# envlogger.net
KiCad netlist of a schematic drawn in EAGLE
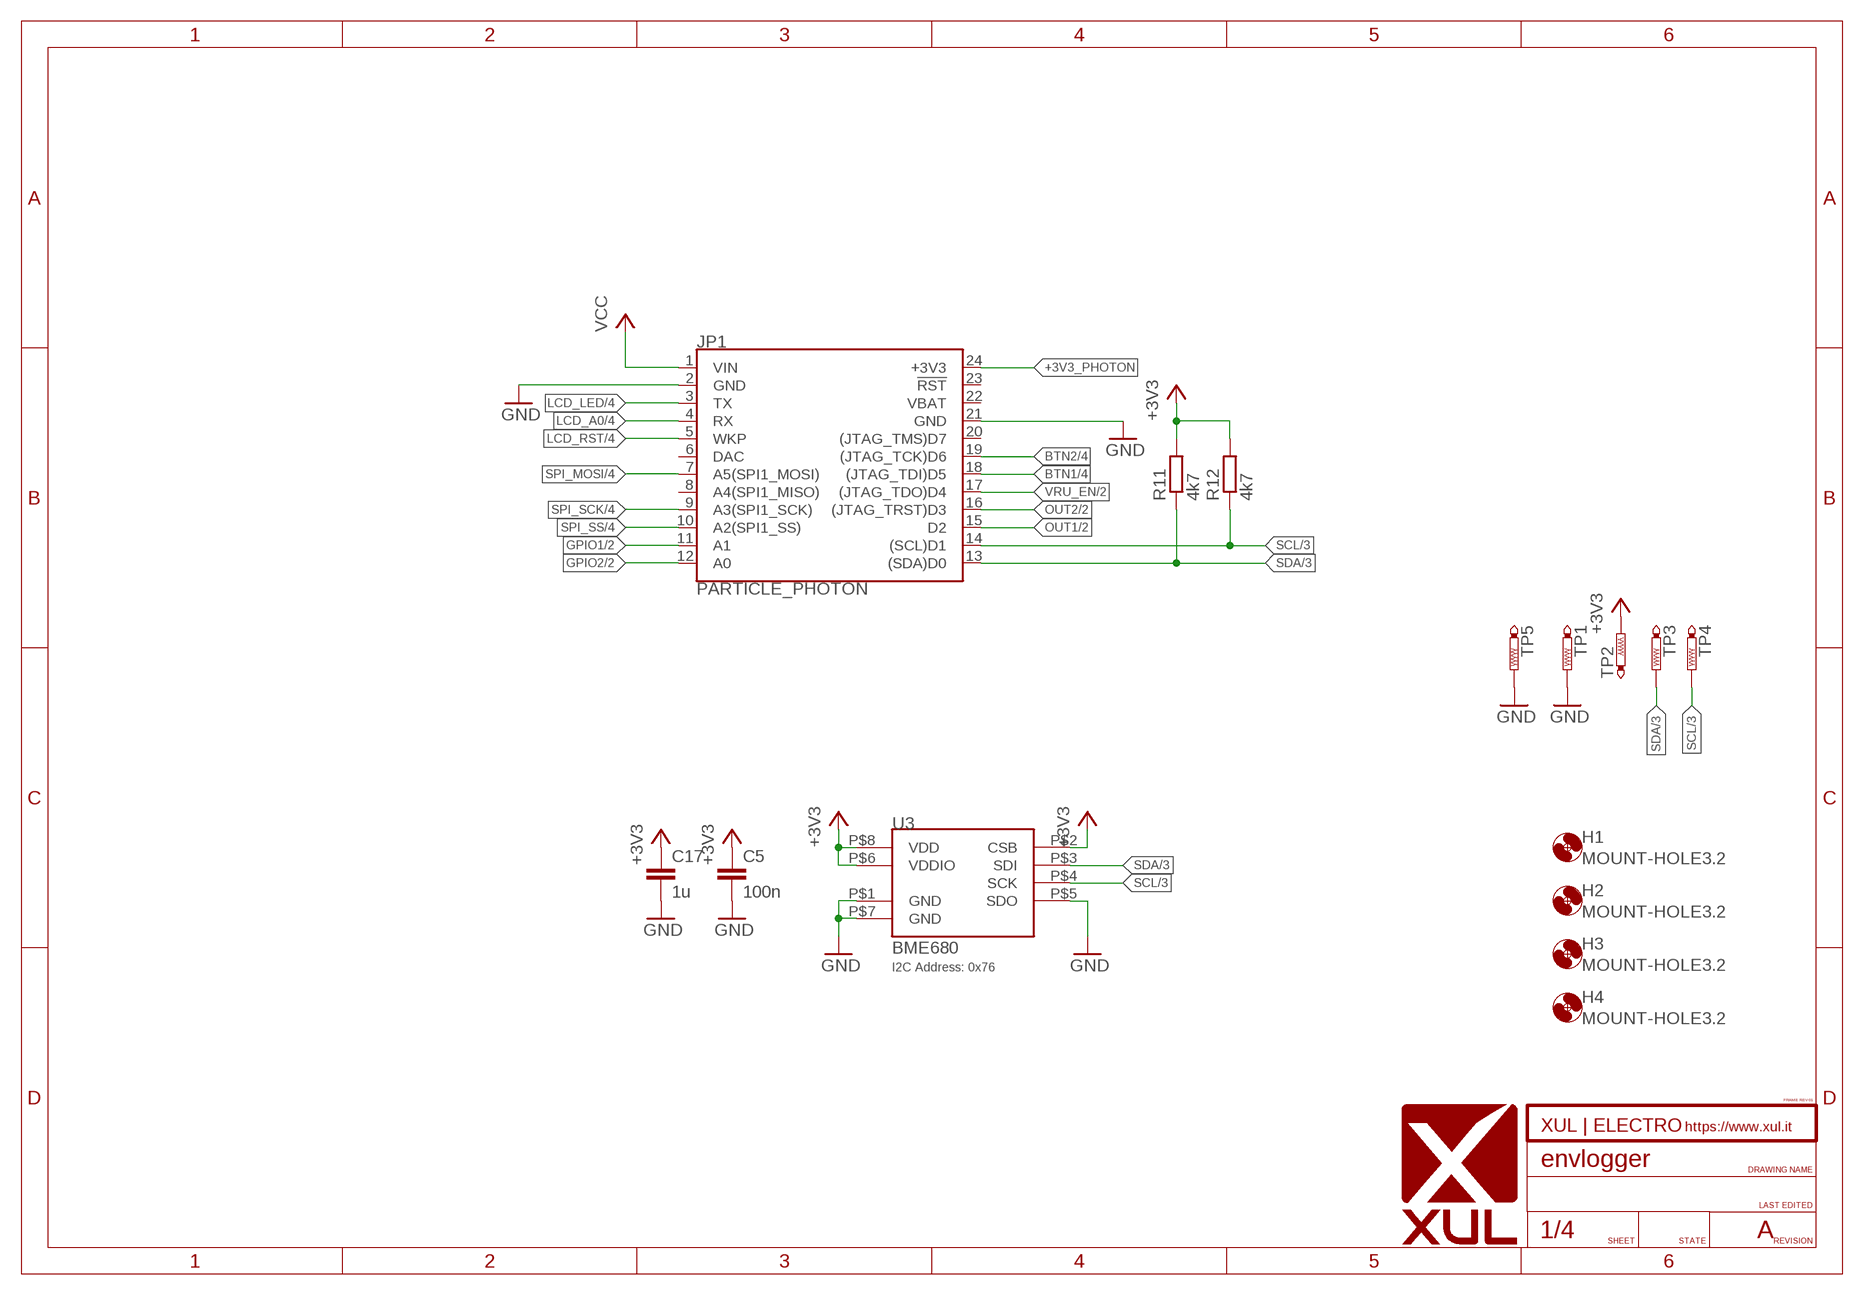
[diagram p0: schematic, sheet 1]
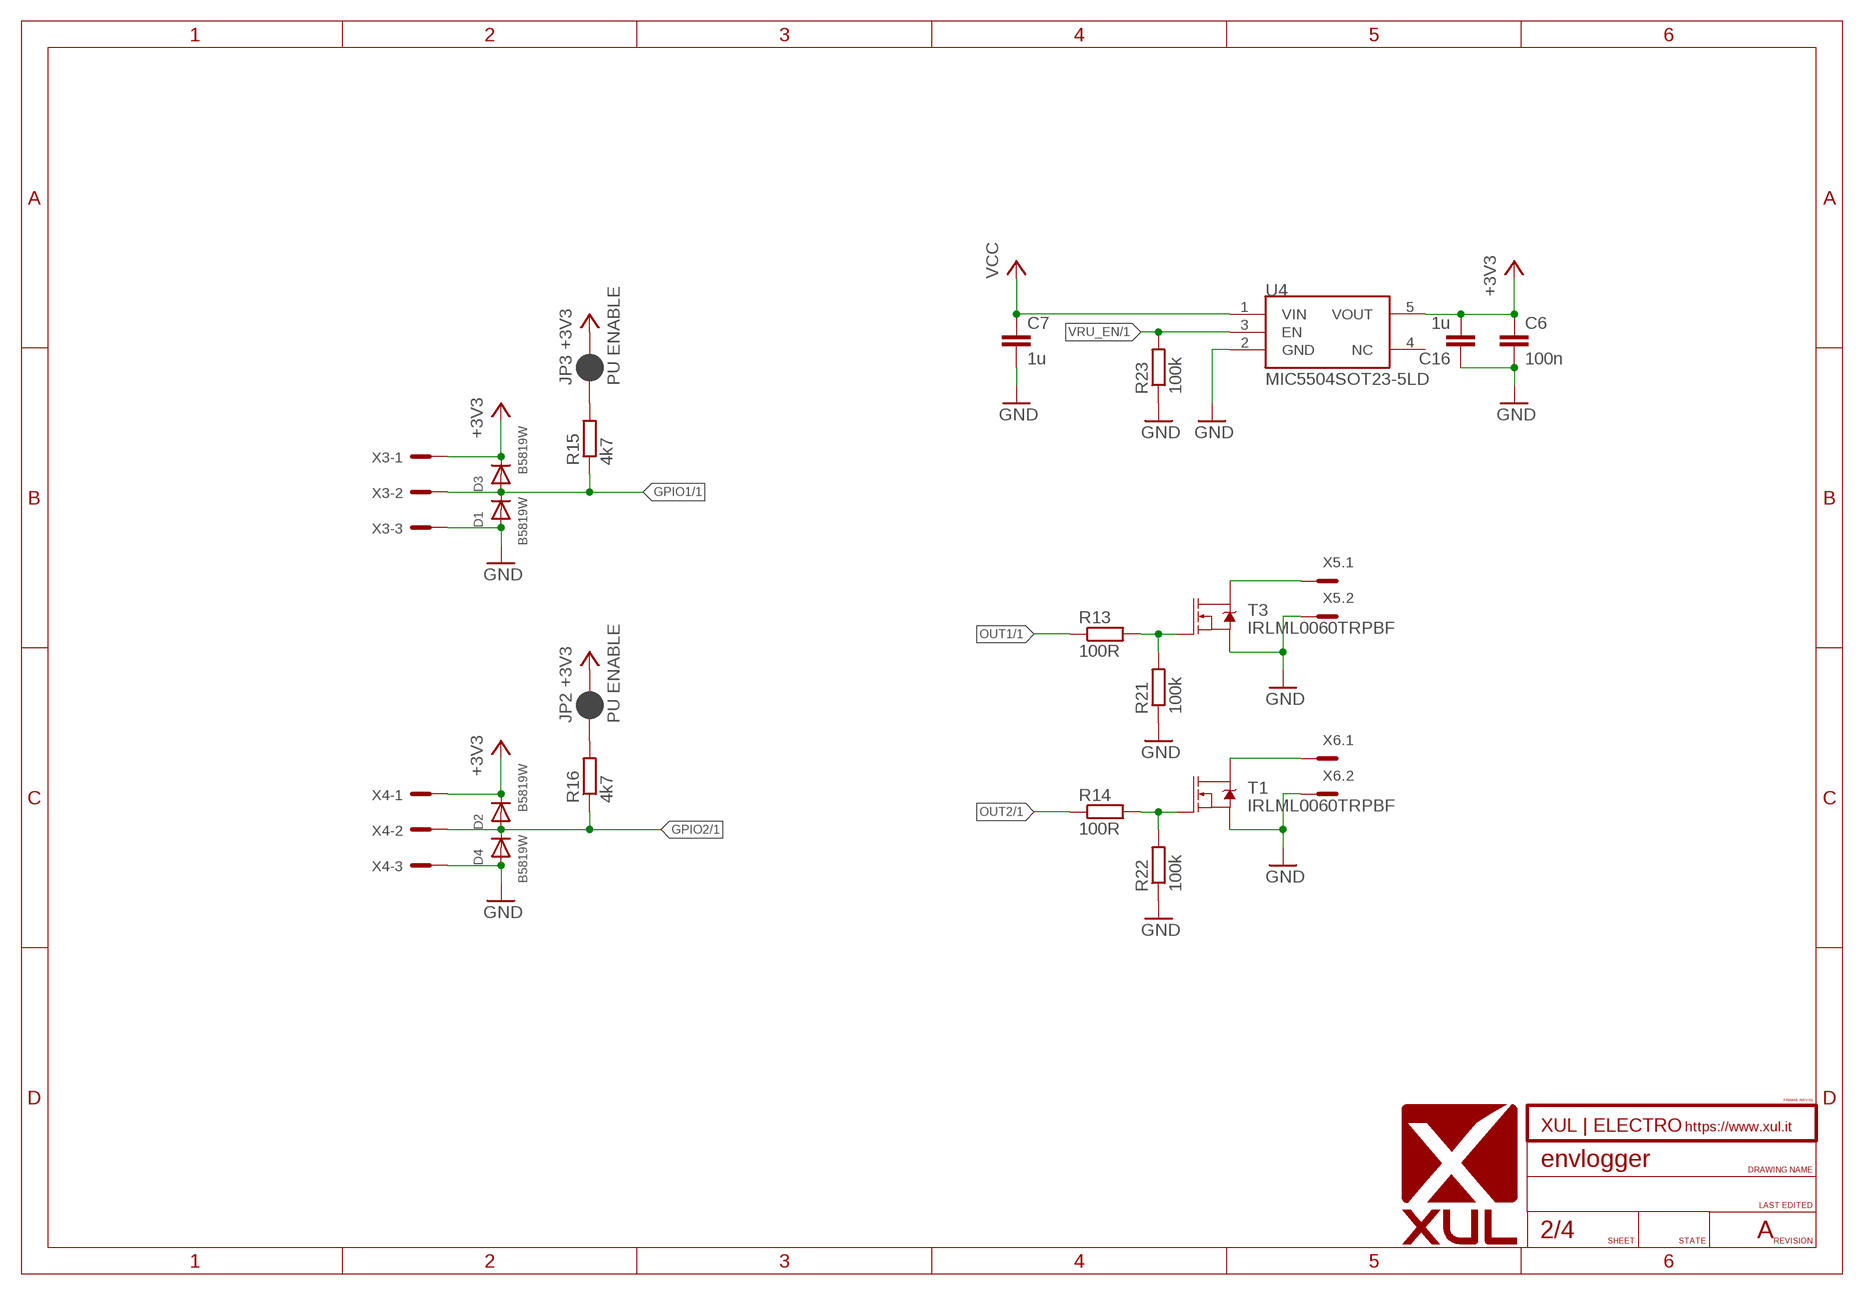
[diagram p1: schematic, sheet 2]
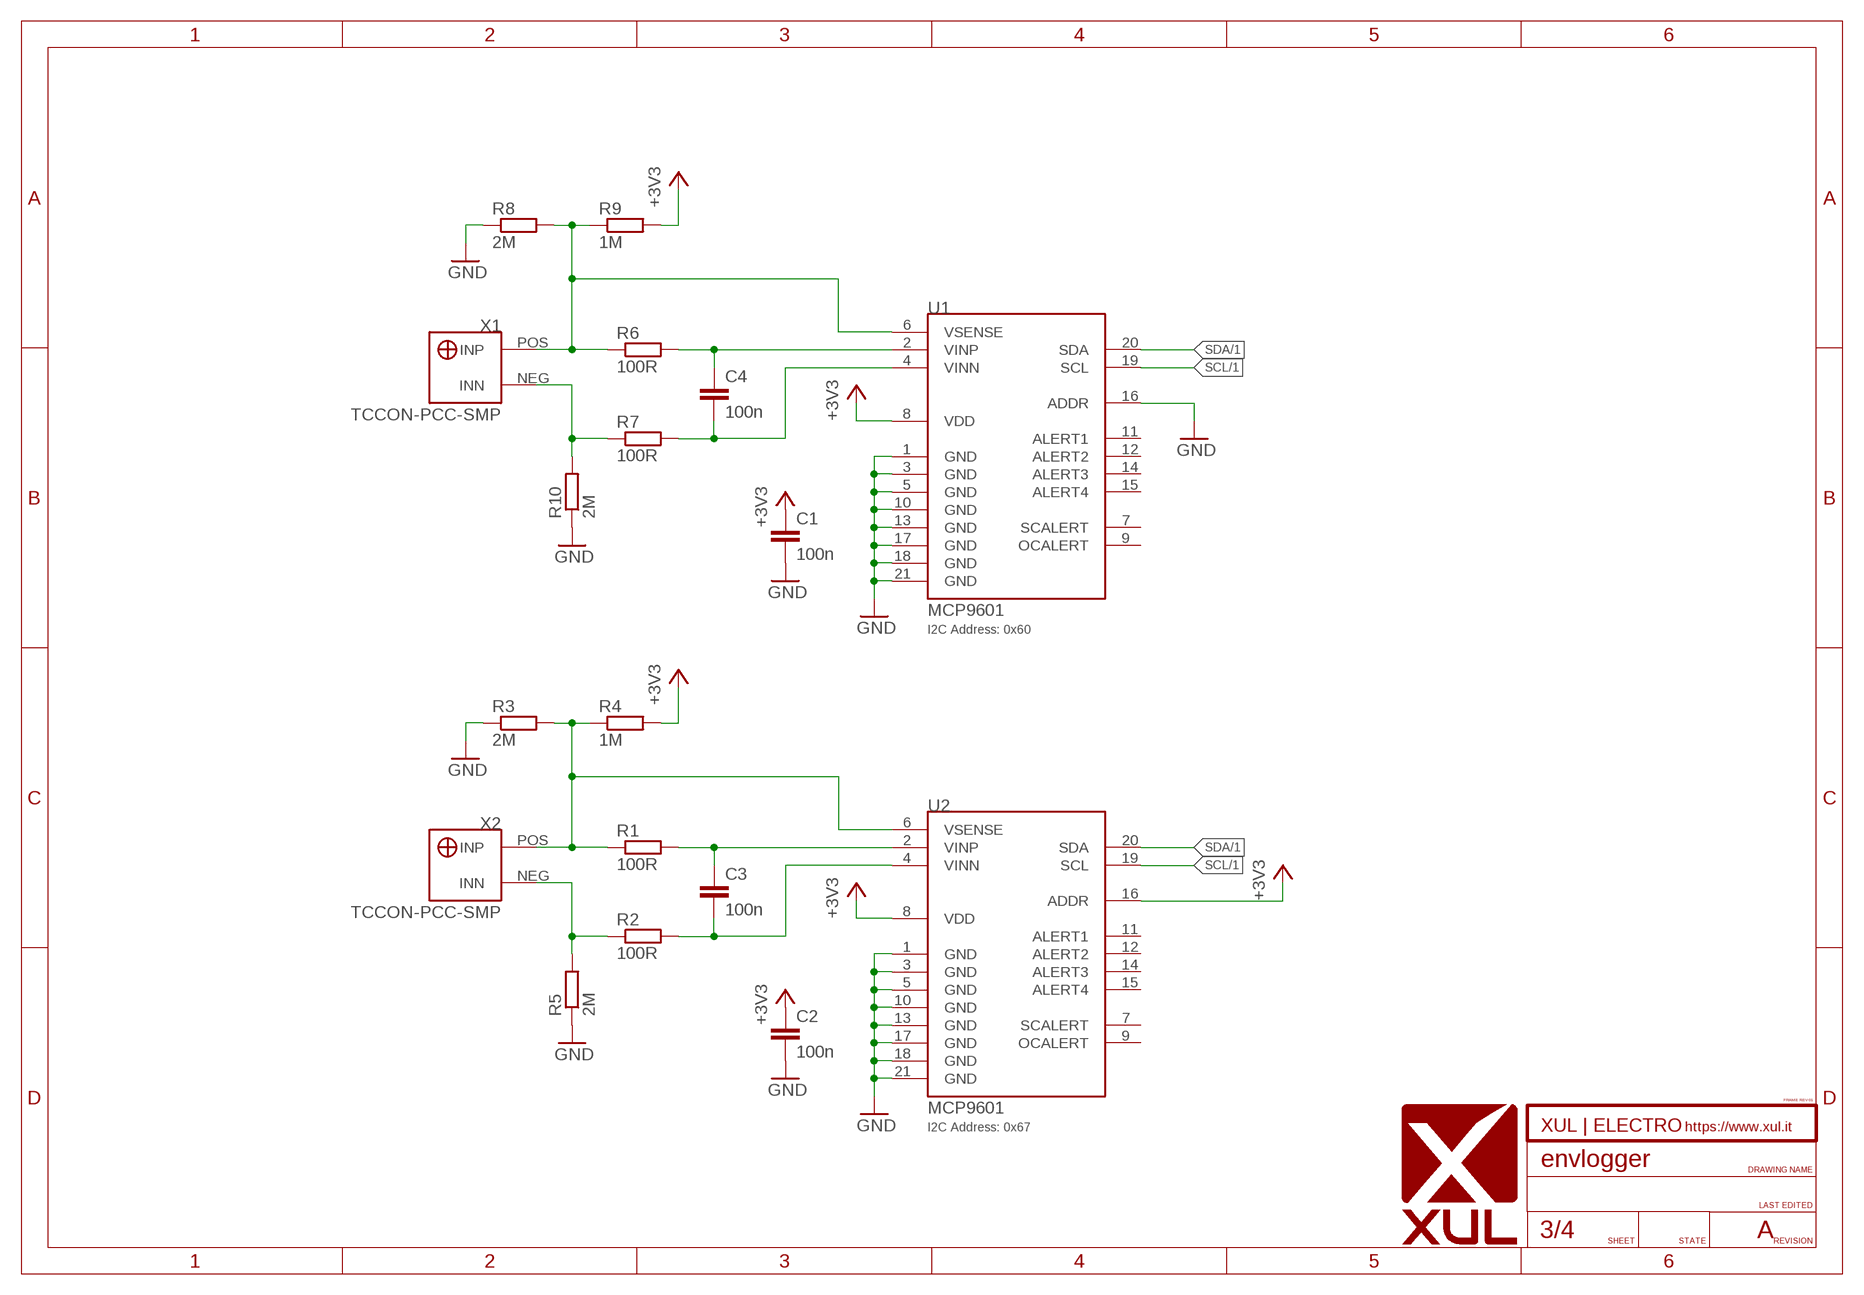
[diagram p2: schematic, sheet 3]
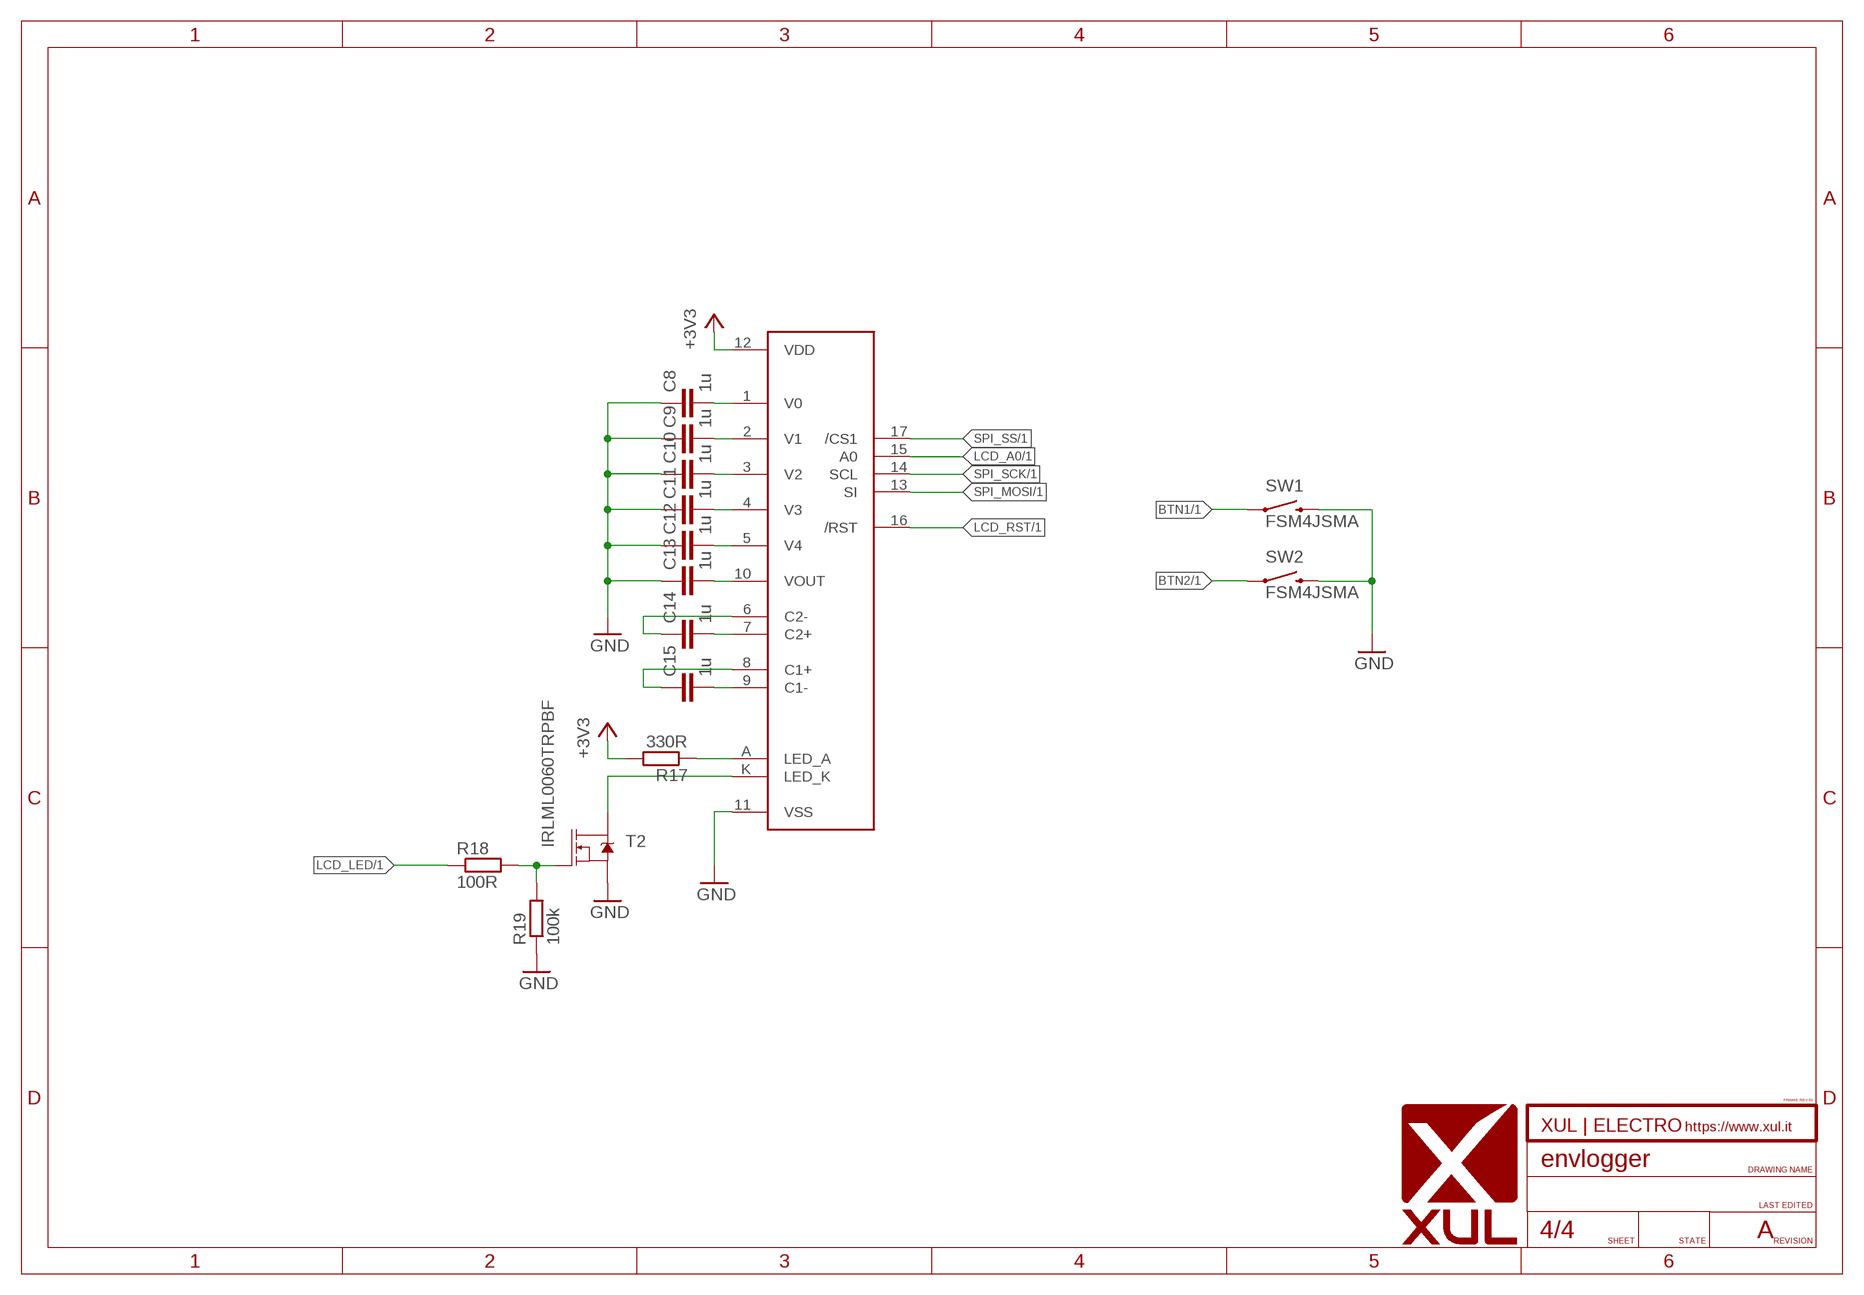
[diagram p3: schematic, sheet 4]

(export (version "E")
  (design (tool "Eeschema 10.0.6"))
  (components
    (comp (ref "C5")
      (value "100n")
      (footprint "eagle-import:C0603")
      (libsource (lib "eagle-import") (part "C-EUC0603"))
    )
    (comp (ref "C17")
      (value "1u")
      (footprint "eagle-import:C0603")
      (libsource (lib "eagle-import") (part "C-EUC0603"))
    )
    (comp (ref "H1")
      (value "MOUNT-HOLE3.2")
      (footprint "eagle-import:3,2")
      (libsource (lib "eagle-import") (part "MOUNT-HOLE3.2"))
    )
    (comp (ref "H2")
      (value "MOUNT-HOLE3.2")
      (footprint "eagle-import:3,2")
      (libsource (lib "eagle-import") (part "MOUNT-HOLE3.2"))
    )
    (comp (ref "H3")
      (value "MOUNT-HOLE3.2")
      (footprint "eagle-import:3,2")
      (libsource (lib "eagle-import") (part "MOUNT-HOLE3.2"))
    )
    (comp (ref "H4")
      (value "MOUNT-HOLE3.2")
      (footprint "eagle-import:3,2")
      (libsource (lib "eagle-import") (part "MOUNT-HOLE3.2"))
    )
    (comp (ref "JP1")
      (value "PARTICLE_PHOTON")
      (footprint "eagle-import:PARTICLE_PHOTON")
      (libsource (lib "eagle-import") (part "PARTICLE_PHOTON"))
    )
    (comp (ref "R11")
      (value "4k7")
      (footprint "eagle-import:R0603")
      (libsource (lib "eagle-import") (part "R-EU_R0603"))
    )
    (comp (ref "R12")
      (value "4k7")
      (footprint "eagle-import:R0603")
      (libsource (lib "eagle-import") (part "R-EU_R0603"))
    )
    (comp (ref "TP1")
      (value "PTR1B1,27")
      (footprint "eagle-import:B1,27")
      (libsource (lib "eagle-import") (part "PTR1B1,27"))
    )
    (comp (ref "TP2")
      (value "PTR1B1,27")
      (footprint "eagle-import:B1,27")
      (libsource (lib "eagle-import") (part "PTR1B1,27"))
    )
    (comp (ref "TP3")
      (value "PTR1B1,27")
      (footprint "eagle-import:B1,27")
      (libsource (lib "eagle-import") (part "PTR1B1,27"))
    )
    (comp (ref "TP4")
      (value "PTR1B1,27")
      (footprint "eagle-import:B1,27")
      (libsource (lib "eagle-import") (part "PTR1B1,27"))
    )
    (comp (ref "TP5")
      (value "PTR1PAD1-13")
      (footprint "eagle-import:P1-13")
      (libsource (lib "eagle-import") (part "PTR1PAD1-13"))
    )
    (comp (ref "U3")
      (value "BME680")
      (footprint "eagle-import:BME680")
      (libsource (lib "eagle-import") (part "BME680"))
    )
    (comp (ref "C6")
      (value "100n")
      (footprint "eagle-import:C0603")
      (libsource (lib "eagle-import") (part "C-EUC0603"))
    )
    (comp (ref "C7")
      (value "1u")
      (footprint "eagle-import:C0603")
      (libsource (lib "eagle-import") (part "C-EUC0603"))
    )
    (comp (ref "C16")
      (value "1u")
      (footprint "eagle-import:C0603")
      (libsource (lib "eagle-import") (part "C-EUC0603"))
    )
    (comp (ref "D1")
      (value "B5819W")
      (footprint "eagle-import:SOD-123")
      (libsource (lib "eagle-import") (part "DIODESOD-123"))
    )
    (comp (ref "D2")
      (value "B5819W")
      (footprint "eagle-import:SOD-123")
      (libsource (lib "eagle-import") (part "DIODESOD-123"))
    )
    (comp (ref "D3")
      (value "B5819W")
      (footprint "eagle-import:SOD-123")
      (libsource (lib "eagle-import") (part "DIODESOD-123"))
    )
    (comp (ref "D4")
      (value "B5819W")
      (footprint "eagle-import:SOD-123")
      (libsource (lib "eagle-import") (part "DIODESOD-123"))
    )
    (comp (ref "JP2")
      (value "PU ENABLE")
      (footprint "eagle-import:SMT-JUMPER_2_NC_PASTE_SILK")
      (libsource (lib "eagle-import") (part "JUMPER-SMT_2_NC_PASTE_SILK"))
    )
    (comp (ref "JP3")
      (value "PU ENABLE")
      (footprint "eagle-import:SMT-JUMPER_2_NC_PASTE_SILK")
      (libsource (lib "eagle-import") (part "JUMPER-SMT_2_NC_PASTE_SILK"))
    )
    (comp (ref "R13")
      (value "100R")
      (footprint "eagle-import:R0603")
      (libsource (lib "eagle-import") (part "R-EU_R0603"))
    )
    (comp (ref "R14")
      (value "100R")
      (footprint "eagle-import:R0603")
      (libsource (lib "eagle-import") (part "R-EU_R0603"))
    )
    (comp (ref "R15")
      (value "4k7")
      (footprint "eagle-import:R0603")
      (libsource (lib "eagle-import") (part "R-EU_R0603"))
    )
    (comp (ref "R16")
      (value "4k7")
      (footprint "eagle-import:R0603")
      (libsource (lib "eagle-import") (part "R-EU_R0603"))
    )
    (comp (ref "R21")
      (value "100k")
      (footprint "eagle-import:R0603")
      (libsource (lib "eagle-import") (part "R-EU_R0603"))
    )
    (comp (ref "R22")
      (value "100k")
      (footprint "eagle-import:R0603")
      (libsource (lib "eagle-import") (part "R-EU_R0603"))
    )
    (comp (ref "R23")
      (value "100k")
      (footprint "eagle-import:R0603")
      (libsource (lib "eagle-import") (part "R-EU_R0603"))
    )
    (comp (ref "T1")
      (value "IRLML0060TRPBF")
      (footprint "eagle-import:SOT95P237X112-3N")
      (libsource (lib "eagle-import") (part "IRLML0060TRPBF"))
    )
    (comp (ref "T3")
      (value "IRLML0060TRPBF")
      (footprint "eagle-import:SOT95P237X112-3N")
      (libsource (lib "eagle-import") (part "IRLML0060TRPBF"))
    )
    (comp (ref "U4")
      (value "MIC5504SOT23-5LD")
      (footprint "eagle-import:SOT95P280X145-5")
      (libsource (lib "eagle-import") (part "MIC5504SOT23-5LD"))
    )
    (comp (ref "X3")
      (value "MCV_05/3-G-2,5")
      (footprint "eagle-import:MC3")
      (libsource (lib "eagle-import") (part "MCV_05/3-G-2,5"))
    )
    (comp (ref "X4")
      (value "MCV_05/3-G-2,5")
      (footprint "eagle-import:MC3")
      (libsource (lib "eagle-import") (part "MCV_05/3-G-2,5"))
    )
    (comp (ref "X5")
      (value "MC2")
      (footprint "eagle-import:MC2")
      (libsource (lib "eagle-import") (part "MC2"))
    )
    (comp (ref "X6")
      (value "MC2")
      (footprint "eagle-import:MC2")
      (libsource (lib "eagle-import") (part "MC2"))
    )
    (comp (ref "C1")
      (value "100n")
      (footprint "eagle-import:C0603")
      (libsource (lib "eagle-import") (part "C-EUC0603"))
    )
    (comp (ref "C2")
      (value "100n")
      (footprint "eagle-import:C0603")
      (libsource (lib "eagle-import") (part "C-EUC0603"))
    )
    (comp (ref "C3")
      (value "100n")
      (footprint "eagle-import:C0603")
      (libsource (lib "eagle-import") (part "C-EUC0603"))
    )
    (comp (ref "C4")
      (value "100n")
      (footprint "eagle-import:C0603")
      (libsource (lib "eagle-import") (part "C-EUC0603"))
    )
    (comp (ref "R1")
      (value "100R")
      (footprint "eagle-import:R0603")
      (libsource (lib "eagle-import") (part "R-EU_R0603"))
    )
    (comp (ref "R2")
      (value "100R")
      (footprint "eagle-import:R0603")
      (libsource (lib "eagle-import") (part "R-EU_R0603"))
    )
    (comp (ref "R3")
      (value "2M")
      (footprint "eagle-import:R0603")
      (libsource (lib "eagle-import") (part "R-EU_R0603"))
    )
    (comp (ref "R4")
      (value "1M")
      (footprint "eagle-import:R0603")
      (libsource (lib "eagle-import") (part "R-EU_R0603"))
    )
    (comp (ref "R5")
      (value "2M")
      (footprint "eagle-import:R0603")
      (libsource (lib "eagle-import") (part "R-EU_R0603"))
    )
    (comp (ref "R6")
      (value "100R")
      (footprint "eagle-import:R0603")
      (libsource (lib "eagle-import") (part "R-EU_R0603"))
    )
    (comp (ref "R7")
      (value "100R")
      (footprint "eagle-import:R0603")
      (libsource (lib "eagle-import") (part "R-EU_R0603"))
    )
    (comp (ref "R8")
      (value "2M")
      (footprint "eagle-import:R0603")
      (libsource (lib "eagle-import") (part "R-EU_R0603"))
    )
    (comp (ref "R9")
      (value "1M")
      (footprint "eagle-import:R0603")
      (libsource (lib "eagle-import") (part "R-EU_R0603"))
    )
    (comp (ref "R10")
      (value "2M")
      (footprint "eagle-import:R0603")
      (libsource (lib "eagle-import") (part "R-EU_R0603"))
    )
    (comp (ref "U1")
      (value "MCP9601")
      (footprint "eagle-import:QFN65P500X500X95-21T325N")
      (libsource (lib "eagle-import") (part "MCP9601"))
    )
    (comp (ref "U2")
      (value "MCP9601")
      (footprint "eagle-import:QFN65P500X500X95-21T325N")
      (libsource (lib "eagle-import") (part "MCP9601"))
    )
    (comp (ref "X1")
      (value "TCCON-PCC-SMP")
      (footprint "eagle-import:TCCON-PCC-SMP")
      (libsource (lib "eagle-import") (part "TCCON-PCC-SMP"))
    )
    (comp (ref "X2")
      (value "TCCON-PCC-SMP")
      (footprint "eagle-import:TCCON-PCC-SMP")
      (libsource (lib "eagle-import") (part "TCCON-PCC-SMP"))
    )
    (comp (ref "C8")
      (value "1u")
      (footprint "eagle-import:C0603")
      (libsource (lib "eagle-import") (part "C-EUC0603"))
    )
    (comp (ref "C9")
      (value "1u")
      (footprint "eagle-import:C0603")
      (libsource (lib "eagle-import") (part "C-EUC0603"))
    )
    (comp (ref "C10")
      (value "1u")
      (footprint "eagle-import:C0603")
      (libsource (lib "eagle-import") (part "C-EUC0603"))
    )
    (comp (ref "C11")
      (value "1u")
      (footprint "eagle-import:C0603")
      (libsource (lib "eagle-import") (part "C-EUC0603"))
    )
    (comp (ref "C12")
      (value "1u")
      (footprint "eagle-import:C0603")
      (libsource (lib "eagle-import") (part "C-EUC0603"))
    )
    (comp (ref "C13")
      (value "1u")
      (footprint "eagle-import:C0603")
      (libsource (lib "eagle-import") (part "C-EUC0603"))
    )
    (comp (ref "C14")
      (value "1u")
      (footprint "eagle-import:C0603")
      (libsource (lib "eagle-import") (part "C-EUC0603"))
    )
    (comp (ref "C15")
      (value "1u")
      (footprint "eagle-import:C0603")
      (libsource (lib "eagle-import") (part "C-EUC0603"))
    )
    (comp (ref "DISP1")
      (value "NHD-C12832A1Z")
      (footprint "eagle-import:NHD-C12832A1Z")
      (libsource (lib "eagle-import") (part "NHD-C12832A1Z"))
    )
    (comp (ref "R17")
      (value "330R")
      (footprint "eagle-import:R0603")
      (libsource (lib "eagle-import") (part "R-EU_R0603"))
    )
    (comp (ref "R18")
      (value "100R")
      (footprint "eagle-import:R0603")
      (libsource (lib "eagle-import") (part "R-EU_R0603"))
    )
    (comp (ref "R19")
      (value "100k")
      (footprint "eagle-import:R0603")
      (libsource (lib "eagle-import") (part "R-EU_R0603"))
    )
    (comp (ref "SW1")
      (value "FSM4JSMA")
      (footprint "eagle-import:BUTTON-6MM-SPST")
      (libsource (lib "eagle-import") (part "FSM4JSMA"))
    )
    (comp (ref "SW2")
      (value "FSM4JSMA")
      (footprint "eagle-import:BUTTON-6MM-SPST")
      (libsource (lib "eagle-import") (part "FSM4JSMA"))
    )
    (comp (ref "T2")
      (value "IRLML0060TRPBF")
      (footprint "eagle-import:SOT95P237X112-3N")
      (libsource (lib "eagle-import") (part "IRLML0060TRPBF"))
    )
  )
  (nets
    (net (code "1") (name "+3V3") (class "Default")
      (node (ref "C1") (pin "1") (pinfunction "1_1") (pintype "passive"))
      (node (ref "C16") (pin "2") (pinfunction "2_2") (pintype "passive"))
      (node (ref "C17") (pin "1") (pinfunction "1_1") (pintype "passive"))
      (node (ref "C2") (pin "1") (pinfunction "1_1") (pintype "passive"))
      (node (ref "C5") (pin "1") (pinfunction "1_1") (pintype "passive"))
      (node (ref "C6") (pin "1") (pinfunction "1_1") (pintype "passive"))
      (node (ref "D2") (pin "C") (pinfunction "C_C") (pintype "passive"))
      (node (ref "D3") (pin "C") (pinfunction "C_C") (pintype "passive"))
      (node (ref "DISP1") (pin "12") (pinfunction "VDD_12") (pintype "bidirectional"))
      (node (ref "JP2") (pin "2") (pinfunction "2_2") (pintype "passive"))
      (node (ref "JP3") (pin "2") (pinfunction "2_2") (pintype "passive"))
      (node (ref "R11") (pin "2") (pinfunction "2_2") (pintype "passive"))
      (node (ref "R12") (pin "2") (pinfunction "2_2") (pintype "passive"))
      (node (ref "R17") (pin "2") (pinfunction "2_2") (pintype "passive"))
      (node (ref "R4") (pin "2") (pinfunction "2_2") (pintype "passive"))
      (node (ref "R9") (pin "2") (pinfunction "2_2") (pintype "passive"))
      (node (ref "TP2") (pin "TP") (pinfunction "TP_TP") (pintype "input"))
      (node (ref "U1") (pin "8") (pinfunction "VDD_8") (pintype "bidirectional"))
      (node (ref "U2") (pin "16") (pinfunction "ADDR_16") (pintype "bidirectional"))
      (node (ref "U2") (pin "8") (pinfunction "VDD_8") (pintype "bidirectional"))
      (node (ref "U3") (pin "P$2") (pinfunction "CSB_P$2") (pintype "bidirectional"))
      (node (ref "U3") (pin "P$6") (pinfunction "VDDIO_P$6") (pintype "bidirectional"))
      (node (ref "U3") (pin "P$8") (pinfunction "VDD_P$8") (pintype "bidirectional"))
      (node (ref "U4") (pin "5") (pinfunction "VOUT_5") (pintype "power_in"))
      (node (ref "X3") (pin "1") (pinfunction "SK_1") (pintype "passive"))
      (node (ref "X4") (pin "1") (pinfunction "SK_1") (pintype "passive"))
    )
    (net (code "2") (name "+3V3_PHOTON") (class "Default")
      (node (ref "JP1") (pin "24") (pinfunction "+3V3_24") (pintype "power_in"))
    )
    (net (code "3") (name "BTN1") (class "Default")
      (node (ref "JP1") (pin "18") (pinfunction "(JTAG_TDI)D5_18") (pintype "bidirectional"))
      (node (ref "SW1") (pin "P$1") (pinfunction "1_P$1") (pintype "passive"))
    )
    (net (code "4") (name "BTN2") (class "Default")
      (node (ref "JP1") (pin "19") (pinfunction "(JTAG_TCK)D6_19") (pintype "bidirectional"))
      (node (ref "SW2") (pin "P$1") (pinfunction "1_P$1") (pintype "passive"))
    )
    (net (code "5") (name "GND") (class "Default")
      (node (ref "C1") (pin "2") (pinfunction "2_2") (pintype "passive"))
      (node (ref "C10") (pin "1") (pinfunction "1_1") (pintype "passive"))
      (node (ref "C11") (pin "1") (pinfunction "1_1") (pintype "passive"))
      (node (ref "C12") (pin "1") (pinfunction "1_1") (pintype "passive"))
      (node (ref "C13") (pin "1") (pinfunction "1_1") (pintype "passive"))
      (node (ref "C16") (pin "1") (pinfunction "1_1") (pintype "passive"))
      (node (ref "C17") (pin "2") (pinfunction "2_2") (pintype "passive"))
      (node (ref "C2") (pin "2") (pinfunction "2_2") (pintype "passive"))
      (node (ref "C5") (pin "2") (pinfunction "2_2") (pintype "passive"))
      (node (ref "C6") (pin "2") (pinfunction "2_2") (pintype "passive"))
      (node (ref "C7") (pin "2") (pinfunction "2_2") (pintype "passive"))
      (node (ref "C8") (pin "1") (pinfunction "1_1") (pintype "passive"))
      (node (ref "C9") (pin "1") (pinfunction "1_1") (pintype "passive"))
      (node (ref "D1") (pin "A") (pinfunction "A_A") (pintype "passive"))
      (node (ref "D4") (pin "A") (pinfunction "A_A") (pintype "passive"))
      (node (ref "DISP1") (pin "11") (pinfunction "VSS_11") (pintype "bidirectional"))
      (node (ref "JP1") (pin "2") (pinfunction "GND_2") (pintype "power_in"))
      (node (ref "JP1") (pin "21") (pinfunction "GND_21") (pintype "power_in"))
      (node (ref "R10") (pin "1") (pinfunction "1_1") (pintype "passive"))
      (node (ref "R19") (pin "1") (pinfunction "1_1") (pintype "passive"))
      (node (ref "R21") (pin "1") (pinfunction "1_1") (pintype "passive"))
      (node (ref "R22") (pin "1") (pinfunction "1_1") (pintype "passive"))
      (node (ref "R23") (pin "1") (pinfunction "1_1") (pintype "passive"))
      (node (ref "R3") (pin "1") (pinfunction "1_1") (pintype "passive"))
      (node (ref "R5") (pin "1") (pinfunction "1_1") (pintype "passive"))
      (node (ref "R8") (pin "1") (pinfunction "1_1") (pintype "passive"))
      (node (ref "SW1") (pin "P$4") (pinfunction "2_P$4") (pintype "passive"))
      (node (ref "SW2") (pin "P$4") (pinfunction "2_P$4") (pintype "passive"))
      (node (ref "T1") (pin "2") (pinfunction "S_2") (pintype "bidirectional"))
      (node (ref "T2") (pin "2") (pinfunction "S_2") (pintype "bidirectional"))
      (node (ref "T3") (pin "2") (pinfunction "S_2") (pintype "bidirectional"))
      (node (ref "TP1") (pin "TP") (pinfunction "TP_TP") (pintype "input"))
      (node (ref "TP5") (pin "TP") (pinfunction "TP_TP") (pintype "input"))
      (node (ref "U1") (pin "1") (pinfunction "GND_1") (pintype "bidirectional"))
      (node (ref "U1") (pin "10") (pinfunction "GND_10") (pintype "bidirectional"))
      (node (ref "U1") (pin "13") (pinfunction "GND_13") (pintype "bidirectional"))
      (node (ref "U1") (pin "16") (pinfunction "ADDR_16") (pintype "bidirectional"))
      (node (ref "U1") (pin "17") (pinfunction "GND_17") (pintype "bidirectional"))
      (node (ref "U1") (pin "18") (pinfunction "GND_18") (pintype "bidirectional"))
      (node (ref "U1") (pin "21") (pinfunction "GND_21") (pintype "bidirectional"))
      (node (ref "U1") (pin "3") (pinfunction "GND_3") (pintype "bidirectional"))
      (node (ref "U1") (pin "5") (pinfunction "GND_5") (pintype "bidirectional"))
      (node (ref "U2") (pin "1") (pinfunction "GND_1") (pintype "bidirectional"))
      (node (ref "U2") (pin "10") (pinfunction "GND_10") (pintype "bidirectional"))
      (node (ref "U2") (pin "13") (pinfunction "GND_13") (pintype "bidirectional"))
      (node (ref "U2") (pin "17") (pinfunction "GND_17") (pintype "bidirectional"))
      (node (ref "U2") (pin "18") (pinfunction "GND_18") (pintype "bidirectional"))
      (node (ref "U2") (pin "21") (pinfunction "GND_21") (pintype "bidirectional"))
      (node (ref "U2") (pin "3") (pinfunction "GND_3") (pintype "bidirectional"))
      (node (ref "U2") (pin "5") (pinfunction "GND_5") (pintype "bidirectional"))
      (node (ref "U3") (pin "P$1") (pinfunction "GND_P$1") (pintype "bidirectional"))
      (node (ref "U3") (pin "P$5") (pinfunction "SDO_P$5") (pintype "bidirectional"))
      (node (ref "U3") (pin "P$7") (pinfunction "GND_P$7") (pintype "bidirectional"))
      (node (ref "U4") (pin "2") (pinfunction "GND_2") (pintype "power_in"))
      (node (ref "X3") (pin "3") (pinfunction "SK_3") (pintype "passive"))
      (node (ref "X4") (pin "3") (pinfunction "SK_3") (pintype "passive"))
      (node (ref "X5") (pin "2") (pinfunction "SK_2") (pintype "passive"))
      (node (ref "X6") (pin "2") (pinfunction "SK_2") (pintype "passive"))
    )
    (net (code "6") (name "GPIO1") (class "Default")
      (node (ref "D1") (pin "C") (pinfunction "C_C") (pintype "passive"))
      (node (ref "D3") (pin "A") (pinfunction "A_A") (pintype "passive"))
      (node (ref "JP1") (pin "11") (pinfunction "A1_11") (pintype "bidirectional"))
      (node (ref "R15") (pin "1") (pinfunction "1_1") (pintype "passive"))
      (node (ref "X3") (pin "2") (pinfunction "SK_2") (pintype "passive"))
    )
    (net (code "7") (name "GPIO2") (class "Default")
      (node (ref "D2") (pin "A") (pinfunction "A_A") (pintype "passive"))
      (node (ref "D4") (pin "C") (pinfunction "C_C") (pintype "passive"))
      (node (ref "JP1") (pin "12") (pinfunction "A0_12") (pintype "bidirectional"))
      (node (ref "R16") (pin "1") (pinfunction "1_1") (pintype "passive"))
      (node (ref "X4") (pin "2") (pinfunction "SK_2") (pintype "passive"))
    )
    (net (code "8") (name "LCD_A0") (class "Default")
      (node (ref "DISP1") (pin "15") (pinfunction "A0_15") (pintype "bidirectional"))
      (node (ref "JP1") (pin "4") (pinfunction "RX_4") (pintype "bidirectional"))
    )
    (net (code "9") (name "LCD_LED") (class "Default")
      (node (ref "JP1") (pin "3") (pinfunction "TX_3") (pintype "bidirectional"))
      (node (ref "R18") (pin "1") (pinfunction "1_1") (pintype "passive"))
    )
    (net (code "10") (name "LCD_RST") (class "Default")
      (node (ref "DISP1") (pin "16") (pinfunction "/RST_16") (pintype "bidirectional"))
      (node (ref "JP1") (pin "5") (pinfunction "WKP_5") (pintype "bidirectional"))
    )
    (net (code "11") (name "Net-(DISP1-C1+)") (class "Default")
      (node (ref "C15") (pin "1") (pinfunction "1_1") (pintype "passive"))
      (node (ref "DISP1") (pin "8") (pinfunction "C1+_8") (pintype "bidirectional"))
    )
    (net (code "12") (name "Net-(DISP1-C1-)") (class "Default")
      (node (ref "C15") (pin "2") (pinfunction "2_2") (pintype "passive"))
      (node (ref "DISP1") (pin "9") (pinfunction "C1-_9") (pintype "bidirectional"))
    )
    (net (code "13") (name "Net-(DISP1-C2+)") (class "Default")
      (node (ref "C14") (pin "2") (pinfunction "2_2") (pintype "passive"))
      (node (ref "DISP1") (pin "7") (pinfunction "C2+_7") (pintype "bidirectional"))
    )
    (net (code "14") (name "Net-(DISP1-C2-)") (class "Default")
      (node (ref "C14") (pin "1") (pinfunction "1_1") (pintype "passive"))
      (node (ref "DISP1") (pin "6") (pinfunction "C2-_6") (pintype "bidirectional"))
    )
    (net (code "15") (name "Net-(DISP1-LED_A)") (class "Default")
      (node (ref "DISP1") (pin "A") (pinfunction "LED_A_A") (pintype "bidirectional"))
      (node (ref "R17") (pin "1") (pinfunction "1_1") (pintype "passive"))
    )
    (net (code "16") (name "Net-(DISP1-LED_K)") (class "Default")
      (node (ref "DISP1") (pin "K") (pinfunction "LED_K_K") (pintype "bidirectional"))
      (node (ref "T2") (pin "3") (pinfunction "D_3") (pintype "bidirectional"))
    )
    (net (code "17") (name "Net-(DISP1-V0)") (class "Default")
      (node (ref "C8") (pin "2") (pinfunction "2_2") (pintype "passive"))
      (node (ref "DISP1") (pin "1") (pinfunction "V0_1") (pintype "bidirectional"))
    )
    (net (code "18") (name "Net-(DISP1-V1)") (class "Default")
      (node (ref "C9") (pin "2") (pinfunction "2_2") (pintype "passive"))
      (node (ref "DISP1") (pin "2") (pinfunction "V1_2") (pintype "bidirectional"))
    )
    (net (code "19") (name "Net-(DISP1-V2)") (class "Default")
      (node (ref "C10") (pin "2") (pinfunction "2_2") (pintype "passive"))
      (node (ref "DISP1") (pin "3") (pinfunction "V2_3") (pintype "bidirectional"))
    )
    (net (code "20") (name "Net-(DISP1-V3)") (class "Default")
      (node (ref "C11") (pin "2") (pinfunction "2_2") (pintype "passive"))
      (node (ref "DISP1") (pin "4") (pinfunction "V3_4") (pintype "bidirectional"))
    )
    (net (code "21") (name "Net-(DISP1-V4)") (class "Default")
      (node (ref "C12") (pin "2") (pinfunction "2_2") (pintype "passive"))
      (node (ref "DISP1") (pin "5") (pinfunction "V4_5") (pintype "bidirectional"))
    )
    (net (code "22") (name "Net-(DISP1-VOUT)") (class "Default")
      (node (ref "C13") (pin "2") (pinfunction "2_2") (pintype "passive"))
      (node (ref "DISP1") (pin "10") (pinfunction "VOUT_10") (pintype "bidirectional"))
    )
    (net (code "23") (name "Net-(JP2-Pad1)") (class "Default")
      (node (ref "JP2") (pin "1") (pinfunction "1_1") (pintype "passive"))
      (node (ref "R16") (pin "2") (pinfunction "2_2") (pintype "passive"))
    )
    (net (code "24") (name "Net-(JP3-Pad1)") (class "Default")
      (node (ref "JP3") (pin "1") (pinfunction "1_1") (pintype "passive"))
      (node (ref "R15") (pin "2") (pinfunction "2_2") (pintype "passive"))
    )
    (net (code "25") (name "Net-(T1-D)") (class "Default")
      (node (ref "T1") (pin "3") (pinfunction "D_3") (pintype "bidirectional"))
      (node (ref "X6") (pin "1") (pinfunction "SK_1") (pintype "passive"))
    )
    (net (code "26") (name "Net-(T1-G)") (class "Default")
      (node (ref "R14") (pin "2") (pinfunction "2_2") (pintype "passive"))
      (node (ref "R22") (pin "2") (pinfunction "2_2") (pintype "passive"))
      (node (ref "T1") (pin "1") (pinfunction "G_1") (pintype "bidirectional"))
    )
    (net (code "27") (name "Net-(T2-G)") (class "Default")
      (node (ref "R18") (pin "2") (pinfunction "2_2") (pintype "passive"))
      (node (ref "R19") (pin "2") (pinfunction "2_2") (pintype "passive"))
      (node (ref "T2") (pin "1") (pinfunction "G_1") (pintype "bidirectional"))
    )
    (net (code "28") (name "Net-(T3-D)") (class "Default")
      (node (ref "T3") (pin "3") (pinfunction "D_3") (pintype "bidirectional"))
      (node (ref "X5") (pin "1") (pinfunction "SK_1") (pintype "passive"))
    )
    (net (code "29") (name "Net-(T3-G)") (class "Default")
      (node (ref "R13") (pin "2") (pinfunction "2_2") (pintype "passive"))
      (node (ref "R21") (pin "2") (pinfunction "2_2") (pintype "passive"))
      (node (ref "T3") (pin "1") (pinfunction "G_1") (pintype "bidirectional"))
    )
    (net (code "30") (name "Net-(U1-VINN)") (class "Default")
      (node (ref "C4") (pin "2") (pinfunction "2_2") (pintype "passive"))
      (node (ref "R7") (pin "2") (pinfunction "2_2") (pintype "passive"))
      (node (ref "U1") (pin "4") (pinfunction "VINN_4") (pintype "bidirectional"))
    )
    (net (code "31") (name "Net-(U1-VINP)") (class "Default")
      (node (ref "C4") (pin "1") (pinfunction "1_1") (pintype "passive"))
      (node (ref "R6") (pin "2") (pinfunction "2_2") (pintype "passive"))
      (node (ref "U1") (pin "2") (pinfunction "VINP_2") (pintype "bidirectional"))
    )
    (net (code "32") (name "Net-(U1-VSENSE)") (class "Default")
      (node (ref "R6") (pin "1") (pinfunction "1_1") (pintype "passive"))
      (node (ref "R8") (pin "2") (pinfunction "2_2") (pintype "passive"))
      (node (ref "R9") (pin "1") (pinfunction "1_1") (pintype "passive"))
      (node (ref "U1") (pin "6") (pinfunction "VSENSE_6") (pintype "bidirectional"))
      (node (ref "X1") (pin "POS") (pinfunction "INP_POS") (pintype "bidirectional"))
    )
    (net (code "33") (name "Net-(U2-VINN)") (class "Default")
      (node (ref "C3") (pin "2") (pinfunction "2_2") (pintype "passive"))
      (node (ref "R2") (pin "2") (pinfunction "2_2") (pintype "passive"))
      (node (ref "U2") (pin "4") (pinfunction "VINN_4") (pintype "bidirectional"))
    )
    (net (code "34") (name "Net-(U2-VINP)") (class "Default")
      (node (ref "C3") (pin "1") (pinfunction "1_1") (pintype "passive"))
      (node (ref "R1") (pin "2") (pinfunction "2_2") (pintype "passive"))
      (node (ref "U2") (pin "2") (pinfunction "VINP_2") (pintype "bidirectional"))
    )
    (net (code "35") (name "Net-(U2-VSENSE)") (class "Default")
      (node (ref "R1") (pin "1") (pinfunction "1_1") (pintype "passive"))
      (node (ref "R3") (pin "2") (pinfunction "2_2") (pintype "passive"))
      (node (ref "R4") (pin "1") (pinfunction "1_1") (pintype "passive"))
      (node (ref "U2") (pin "6") (pinfunction "VSENSE_6") (pintype "bidirectional"))
      (node (ref "X2") (pin "POS") (pinfunction "INP_POS") (pintype "bidirectional"))
    )
    (net (code "36") (name "Net-(X1-INN)") (class "Default")
      (node (ref "R10") (pin "2") (pinfunction "2_2") (pintype "passive"))
      (node (ref "R7") (pin "1") (pinfunction "1_1") (pintype "passive"))
      (node (ref "X1") (pin "NEG") (pinfunction "INN_NEG") (pintype "bidirectional"))
    )
    (net (code "37") (name "Net-(X2-INN)") (class "Default")
      (node (ref "R2") (pin "1") (pinfunction "1_1") (pintype "passive"))
      (node (ref "R5") (pin "2") (pinfunction "2_2") (pintype "passive"))
      (node (ref "X2") (pin "NEG") (pinfunction "INN_NEG") (pintype "bidirectional"))
    )
    (net (code "38") (name "OUT1") (class "Default")
      (node (ref "JP1") (pin "15") (pinfunction "D2_15") (pintype "bidirectional"))
      (node (ref "R13") (pin "1") (pinfunction "1_1") (pintype "passive"))
    )
    (net (code "39") (name "OUT2") (class "Default")
      (node (ref "JP1") (pin "16") (pinfunction "(JTAG_TRST)D3_16") (pintype "bidirectional"))
      (node (ref "R14") (pin "1") (pinfunction "1_1") (pintype "passive"))
    )
    (net (code "40") (name "SCL") (class "Default")
      (node (ref "JP1") (pin "14") (pinfunction "(SCL)D1_14") (pintype "bidirectional"))
      (node (ref "R12") (pin "1") (pinfunction "1_1") (pintype "passive"))
      (node (ref "TP4") (pin "TP") (pinfunction "TP_TP") (pintype "input"))
      (node (ref "U1") (pin "19") (pinfunction "SCL_19") (pintype "bidirectional"))
      (node (ref "U2") (pin "19") (pinfunction "SCL_19") (pintype "bidirectional"))
      (node (ref "U3") (pin "P$4") (pinfunction "SCK_P$4") (pintype "bidirectional"))
    )
    (net (code "41") (name "SDA") (class "Default")
      (node (ref "JP1") (pin "13") (pinfunction "(SDA)D0_13") (pintype "bidirectional"))
      (node (ref "R11") (pin "1") (pinfunction "1_1") (pintype "passive"))
      (node (ref "TP3") (pin "TP") (pinfunction "TP_TP") (pintype "input"))
      (node (ref "U1") (pin "20") (pinfunction "SDA_20") (pintype "bidirectional"))
      (node (ref "U2") (pin "20") (pinfunction "SDA_20") (pintype "bidirectional"))
      (node (ref "U3") (pin "P$3") (pinfunction "SDI_P$3") (pintype "bidirectional"))
    )
    (net (code "42") (name "SPI_MOSI") (class "Default")
      (node (ref "DISP1") (pin "13") (pinfunction "SI_13") (pintype "bidirectional"))
      (node (ref "JP1") (pin "7") (pinfunction "A5(SPI1_MOSI)_7") (pintype "bidirectional"))
    )
    (net (code "43") (name "SPI_SCK") (class "Default")
      (node (ref "DISP1") (pin "14") (pinfunction "SCL_14") (pintype "bidirectional"))
      (node (ref "JP1") (pin "9") (pinfunction "A3(SPI1_SCK)_9") (pintype "bidirectional"))
    )
    (net (code "44") (name "SPI_SS") (class "Default")
      (node (ref "DISP1") (pin "17") (pinfunction "/CS1_17") (pintype "bidirectional"))
      (node (ref "JP1") (pin "10") (pinfunction "A2(SPI1_SS)_10") (pintype "bidirectional"))
    )
    (net (code "45") (name "VBAT") (class "Default")
      (node (ref "JP1") (pin "22") (pinfunction "VBAT_22") (pintype "power_in"))
    )
    (net (code "46") (name "VCC") (class "Default")
      (node (ref "C7") (pin "1") (pinfunction "1_1") (pintype "passive"))
      (node (ref "JP1") (pin "1") (pinfunction "VIN_1") (pintype "power_in"))
      (node (ref "U4") (pin "1") (pinfunction "VIN_1") (pintype "power_in"))
    )
    (net (code "47") (name "VRU_EN") (class "Default")
      (node (ref "JP1") (pin "17") (pinfunction "(JTAG_TDO)D4_17") (pintype "bidirectional"))
      (node (ref "R23") (pin "2") (pinfunction "2_2") (pintype "passive"))
      (node (ref "U4") (pin "3") (pinfunction "EN_3") (pintype "bidirectional"))
    )
    (net (code "48") (name "unconnected-(JP1-(JTAG_TMS)D7-Pad20)") (class "Default")
      (node (ref "JP1") (pin "20") (pinfunction "(JTAG_TMS)D7_20") (pintype "bidirectional"))
    )
    (net (code "49") (name "unconnected-(JP1-A4(SPI1_MISO)-Pad8)") (class "Default")
      (node (ref "JP1") (pin "8") (pinfunction "A4(SPI1_MISO)_8") (pintype "bidirectional"))
    )
    (net (code "50") (name "unconnected-(JP1-DAC-Pad6)") (class "Default")
      (node (ref "JP1") (pin "6") (pinfunction "DAC_6") (pintype "bidirectional"))
    )
    (net (code "51") (name "unconnected-(JP1-~{RST}-Pad23)") (class "Default")
      (node (ref "JP1") (pin "23") (pinfunction "~{RST}_23") (pintype "bidirectional"))
    )
    (net (code "52") (name "unconnected-(U1-ALERT1-Pad11)") (class "Default")
      (node (ref "U1") (pin "11") (pinfunction "ALERT1_11") (pintype "bidirectional"))
    )
    (net (code "53") (name "unconnected-(U1-ALERT2-Pad12)") (class "Default")
      (node (ref "U1") (pin "12") (pinfunction "ALERT2_12") (pintype "bidirectional"))
    )
    (net (code "54") (name "unconnected-(U1-ALERT3-Pad14)") (class "Default")
      (node (ref "U1") (pin "14") (pinfunction "ALERT3_14") (pintype "bidirectional"))
    )
    (net (code "55") (name "unconnected-(U1-ALERT4-Pad15)") (class "Default")
      (node (ref "U1") (pin "15") (pinfunction "ALERT4_15") (pintype "bidirectional"))
    )
    (net (code "56") (name "unconnected-(U1-OCALERT-Pad9)") (class "Default")
      (node (ref "U1") (pin "9") (pinfunction "OCALERT_9") (pintype "bidirectional"))
    )
    (net (code "57") (name "unconnected-(U1-SCALERT-Pad7)") (class "Default")
      (node (ref "U1") (pin "7") (pinfunction "SCALERT_7") (pintype "bidirectional"))
    )
    (net (code "58") (name "unconnected-(U2-ALERT1-Pad11)") (class "Default")
      (node (ref "U2") (pin "11") (pinfunction "ALERT1_11") (pintype "bidirectional"))
    )
    (net (code "59") (name "unconnected-(U2-ALERT2-Pad12)") (class "Default")
      (node (ref "U2") (pin "12") (pinfunction "ALERT2_12") (pintype "bidirectional"))
    )
    (net (code "60") (name "unconnected-(U2-ALERT3-Pad14)") (class "Default")
      (node (ref "U2") (pin "14") (pinfunction "ALERT3_14") (pintype "bidirectional"))
    )
    (net (code "61") (name "unconnected-(U2-ALERT4-Pad15)") (class "Default")
      (node (ref "U2") (pin "15") (pinfunction "ALERT4_15") (pintype "bidirectional"))
    )
    (net (code "62") (name "unconnected-(U2-OCALERT-Pad9)") (class "Default")
      (node (ref "U2") (pin "9") (pinfunction "OCALERT_9") (pintype "bidirectional"))
    )
    (net (code "63") (name "unconnected-(U2-SCALERT-Pad7)") (class "Default")
      (node (ref "U2") (pin "7") (pinfunction "SCALERT_7") (pintype "bidirectional"))
    )
    (net (code "64") (name "unconnected-(U4-NC-Pad4)") (class "Default")
      (node (ref "U4") (pin "4") (pinfunction "NC_4") (pintype "no_connect"))
    )
  )
)
